# 4_Power_Management.net
KiCad netlist of a schematic drawn in Altium Designer
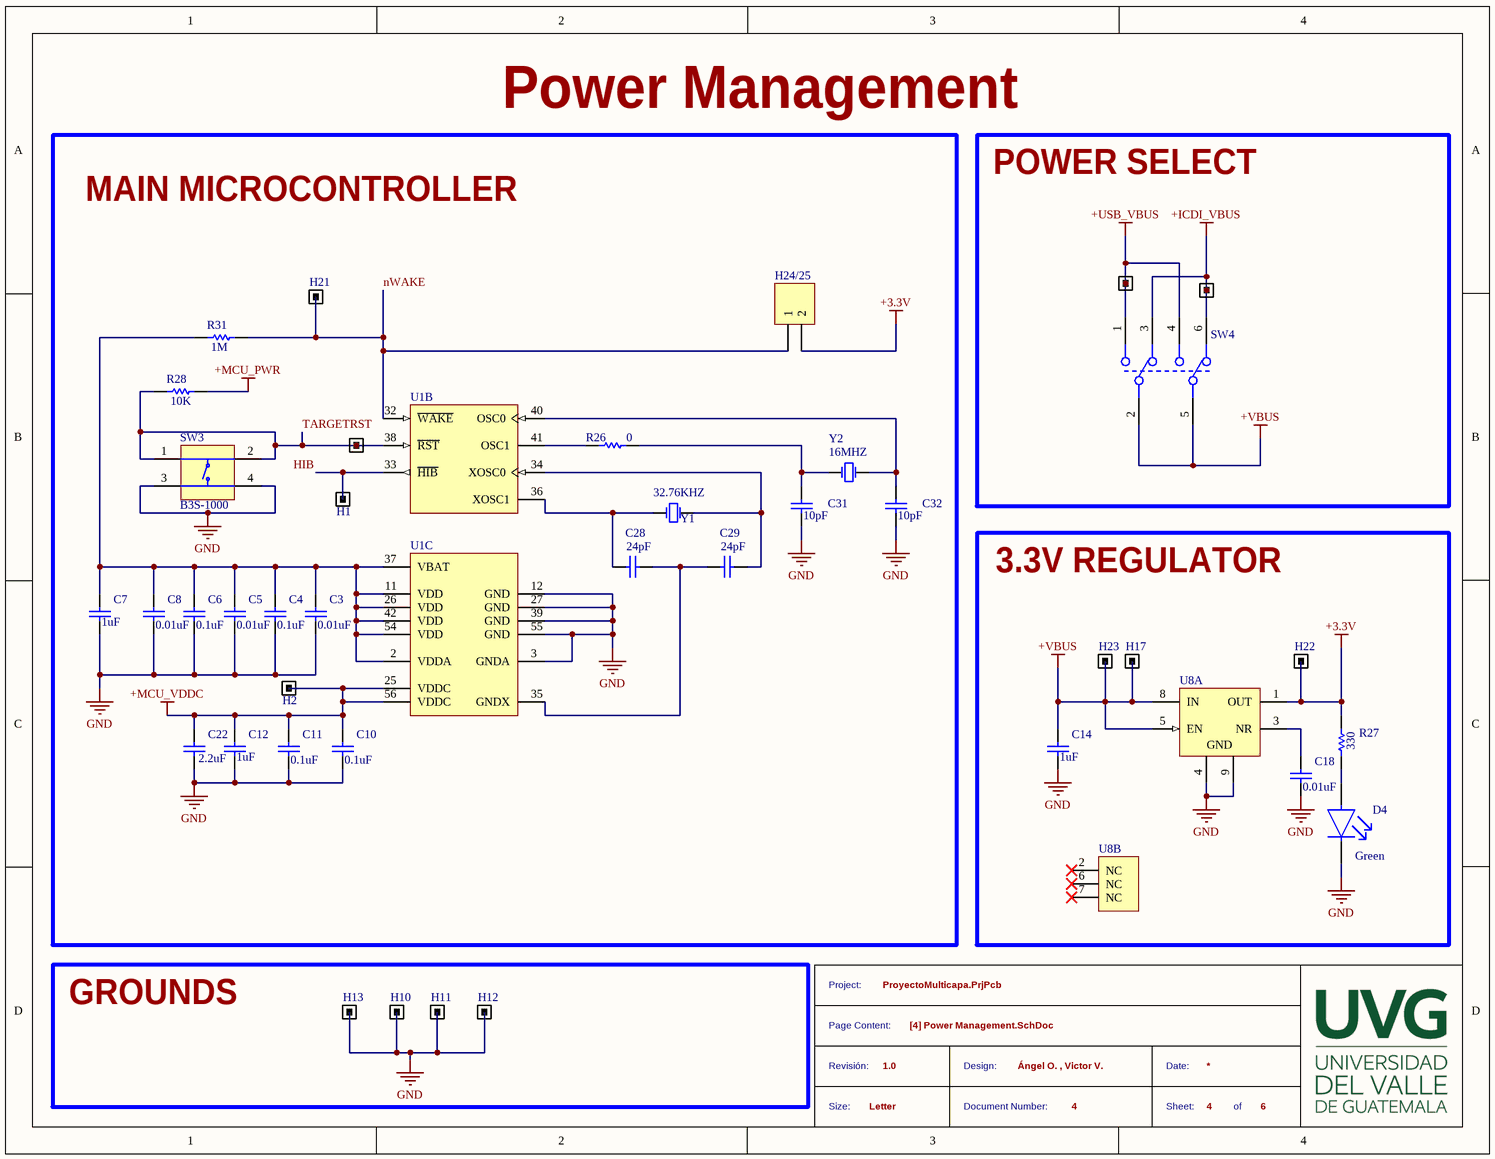
[diagram p0: [4] Power Management.SchDoc]

(export (version "E")
  (design (tool "Eeschema 10.0.6"))
  (components
    (comp (ref "C3")
      (value "EMK105B7103KV-F")
      (footprint "CAPC1005")
      (description "TAIYO YUDEN   EMK105B7103KV-F   CERAMIC CAPACITOR, 0.01UF, 16V, X7R, 10%, 0402, FULL REEL")
      (fields (field (name "MANUFACTURER") "Taiyo Yuden") (field (name "TOLERANCE") "10%"))
      (libsource (lib "LiberiaTivaC") (part "EMK105B7103KV-F"))
    )
    (comp (ref "C4")
      (value "EMK105B7104KV-F")
      (footprint "CAPC1005")
      (fields (field (name "MANUFACTURER") "Taiyo Yuden") (field (name "TOLERANCE") "10%"))
      (libsource (lib "LiberiaTivaC") (part "EMK105B7104KV-F"))
    )
    (comp (ref "C5")
      (value "EMK105B7103KV-F")
      (footprint "CAPC1005")
      (description "TAIYO YUDEN   EMK105B7103KV-F   CERAMIC CAPACITOR, 0.01UF, 16V, X7R, 10%, 0402, FULL REEL")
      (fields (field (name "MANUFACTURER") "Taiyo Yuden") (field (name "TOLERANCE") "10%"))
      (libsource (lib "LiberiaTivaC") (part "EMK105B7103KV-F"))
    )
    (comp (ref "C6")
      (value "EMK105B7104KV-F")
      (footprint "CAPC1005")
      (fields (field (name "MANUFACTURER") "Taiyo Yuden") (field (name "TOLERANCE") "10%"))
      (libsource (lib "LiberiaTivaC") (part "EMK105B7104KV-F"))
    )
    (comp (ref "C7")
      (value "capacitor Johanson Dielectrics Inc")
      (footprint "C0402 imperial")
      (description "Cap Ceramic 1uF 10V X5R 10% SMD 0402 85C T/R")
      (fields
        (field (name "MANUFACTURER") "Johanson")
        (field (name "MANUFACTURER PART NUMBER") "100R07X105KV4T")
      )
      (libsource (lib "Components") (part "100R07X105KV4T"))
    )
    (comp (ref "C8")
      (value "EMK105B7103KV-F")
      (footprint "CAPC1005")
      (description "TAIYO YUDEN   EMK105B7103KV-F   CERAMIC CAPACITOR, 0.01UF, 16V, X7R, 10%, 0402, FULL REEL")
      (fields (field (name "MANUFACTURER") "Taiyo Yuden") (field (name "TOLERANCE") "10%"))
      (libsource (lib "LiberiaTivaC") (part "EMK105B7103KV-F"))
    )
    (comp (ref "C10")
      (value "EMK105B7104KV-F")
      (footprint "CAPC1005")
      (fields (field (name "MANUFACTURER") "Taiyo Yuden") (field (name "TOLERANCE") "10%"))
      (libsource (lib "LiberiaTivaC") (part "EMK105B7104KV-F"))
    )
    (comp (ref "C11")
      (value "EMK105B7104KV-F")
      (footprint "CAPC1005")
      (fields (field (name "MANUFACTURER") "Taiyo Yuden") (field (name "TOLERANCE") "10%"))
      (libsource (lib "LiberiaTivaC") (part "EMK105B7104KV-F"))
    )
    (comp (ref "C12")
      (value "capacitor Johanson Dielectrics Inc")
      (footprint "C0402 imperial")
      (description "Cap Ceramic 1uF 10V X5R 10% SMD 0402 85C T/R")
      (fields
        (field (name "MANUFACTURER") "Johanson")
        (field (name "MANUFACTURER PART NUMBER") "100R07X105KV4T")
      )
      (libsource (lib "Components") (part "100R07X105KV4T"))
    )
    (comp (ref "C14")
      (value "capacitor Johanson Dielectrics Inc")
      (footprint "C0402 imperial")
      (description "Cap Ceramic 1uF 10V X5R 10% SMD 0402 85C T/R")
      (fields
        (field (name "MANUFACTURER") "Johanson")
        (field (name "MANUFACTURER PART NUMBER") "100R07X105KV4T")
      )
      (libsource (lib "Components") (part "100R07X105KV4T"))
    )
    (comp (ref "C18")
      (value "EMK105B7103KV-F")
      (footprint "CAPC1005")
      (description "TAIYO YUDEN   EMK105B7103KV-F   CERAMIC CAPACITOR, 0.01UF, 16V, X7R, 10%, 0402, FULL REEL")
      (fields (field (name "MANUFACTURER") "Taiyo Yuden") (field (name "TOLERANCE") "10%"))
      (libsource (lib "LiberiaTivaC") (part "EMK105B7103KV-F"))
    )
    (comp (ref "C22")
      (value "GRM188R61C225KE15D")
      (footprint "CAPC1608X90X35LL10T15")
      (description "Cap Ceramic 2.2uF 16V X5R 10% SMD 0603 85C Paper T/R")
      (fields (field (name "MANUFACTURER") "Murata") (field (name "TOLERANCE") "10%"))
      (libsource (lib "LiberiaTivaC") (part "GRM188R61C225KE15D"))
    )
    (comp (ref "C28")
      (value "Capacitor")
      (footprint "C0402 imperial")
      (description "CAP CER 24PF 50V C0G 0402")
      (fields (field (name "MANUFACTURER") "TDK") (field (name "MANUFACTURER PART NUMBER") "C1005C0G1H240J"))
      (libsource (lib "LiberiaTivaC") (part "C1005C0G1H240J"))
    )
    (comp (ref "C29")
      (value "Capacitor")
      (footprint "C0402 imperial")
      (description "CAP CER 24PF 50V C0G 0402")
      (fields (field (name "MANUFACTURER") "TDK") (field (name "MANUFACTURER PART NUMBER") "C1005C0G1H240J"))
      (libsource (lib "LiberiaTivaC") (part "C1005C0G1H240J"))
    )
    (comp (ref "C31")
      (value "GRM1555C1H100JZ01D")
      (footprint "CAPC1005X55X25LL05T10")
      (description "CAP, CERAMIC, 10PF, 50V, C0G/NP0, 0402")
      (fields (field (name "MANUFACTURER") "Murata") (field (name "TOLERANCE") "5%"))
      (libsource (lib "LiberiaTivaC") (part "GRM1555C1H100JZ01D"))
    )
    (comp (ref "C32")
      (value "GRM1555C1H100JZ01D")
      (footprint "CAPC1005X55X25LL05T10")
      (description "CAP, CERAMIC, 10PF, 50V, C0G/NP0, 0402")
      (fields (field (name "MANUFACTURER") "Murata") (field (name "TOLERANCE") "5%"))
      (libsource (lib "LiberiaTivaC") (part "GRM1555C1H100JZ01D"))
    )
    (comp (ref "D4")
      (value "Green")
      (footprint "FP-LTST-C171GKT-MFG")
      (description "LED GREEN CLEAR CHIP SMD")
      (fields
        (field (name "MANUFACTURER") "Vishay Lite-On")
        (field (name "MANUFACTURER PART NUMBER") "LTST-C171GKT")
      )
      (libsource (lib "LiberiaTivaC") (part "LTST-C171GKT"))
    )
    (comp (ref "H1")
      (value "header")
      (footprint "HEADER 1")
      (description "Pads header que aparecen en la tiva")
      (libsource (lib "LiberiaTivaC") (part "header"))
    )
    (comp (ref "H2")
      (value "header")
      (footprint "HEADER 1")
      (description "Pads header que aparecen en la tiva")
      (libsource (lib "LiberiaTivaC") (part "header"))
    )
    (comp (ref "H10")
      (value "header")
      (footprint "HEADER 1")
      (description "Pads header que aparecen en la tiva")
      (libsource (lib "LiberiaTivaC") (part "header"))
    )
    (comp (ref "H11")
      (value "header")
      (footprint "HEADER 1")
      (description "Pads header que aparecen en la tiva")
      (libsource (lib "LiberiaTivaC") (part "header"))
    )
    (comp (ref "H12")
      (value "header")
      (footprint "HEADER 1")
      (description "Pads header que aparecen en la tiva")
      (libsource (lib "LiberiaTivaC") (part "header"))
    )
    (comp (ref "H13")
      (value "header")
      (footprint "HEADER 1")
      (description "Pads header que aparecen en la tiva")
      (libsource (lib "LiberiaTivaC") (part "header"))
    )
    (comp (ref "H17")
      (value "header")
      (footprint "HEADER 1")
      (description "Pads header que aparecen en la tiva")
      (libsource (lib "LiberiaTivaC") (part "header"))
    )
    (comp (ref "H18")
      (value "header")
      (footprint "HEADER 1")
      (description "Pads header que aparecen en la tiva")
      (libsource (lib "LiberiaTivaC") (part "header"))
    )
    (comp (ref "H19")
      (value "header")
      (footprint "HEADER 1")
      (description "Pads header que aparecen en la tiva")
      (libsource (lib "LiberiaTivaC") (part "header"))
    )
    (comp (ref "H20")
      (value "header")
      (footprint "HEADER 1")
      (description "Pads header que aparecen en la tiva")
      (libsource (lib "LiberiaTivaC") (part "header"))
    )
    (comp (ref "H21")
      (value "header")
      (footprint "HEADER 1")
      (description "Pads header que aparecen en la tiva")
      (libsource (lib "LiberiaTivaC") (part "header"))
    )
    (comp (ref "H22")
      (value "header")
      (footprint "HEADER 1")
      (description "Pads header que aparecen en la tiva")
      (libsource (lib "LiberiaTivaC") (part "header"))
    )
    (comp (ref "H23")
      (value "header")
      (footprint "HEADER 1")
      (description "Pads header que aparecen en la tiva")
      (libsource (lib "LiberiaTivaC") (part "header"))
    )
    (comp (ref "H24/25")
      (value "Header 2")
      (footprint "HDR1X2")
      (description "Header, 2-Pin")
      (fields (field (name "PUBLISHER") "Altium Limited"))
      (libsource (lib "LiberiaTivaC") (part "Header 2"))
    )
    (comp (ref "R26")
      (value "ERJ-3GEY0R00V")
      (footprint "FP-ERJ-3GEY0R00V-IPC_A")
      (description "Res Thick Film 0603 0 Ohm Jumper Molded SMD Punched Carrier T/R")
      (fields (field (name "MANUFACTURER") "Panasonic") (field (name "TOLERANCE") "0%"))
      (libsource (lib "LiberiaTivaC") (part "ERJ-3GEY0R00V"))
    )
    (comp (ref "R27")
      (value "RC0402FR-07330RL")
      (footprint "RESC1005X40X25LL05T10")
      (description "Res Thick Film 0402 330 Ohm 1% 0.063W(1/16W) ±100ppm/C Pad SMD T/R")
      (fields (field (name "MANUFACTURER") "Yageo / Phycomp") (field (name "TOLERANCE") "1%"))
      (libsource (lib "LiberiaTivaC") (part "RC0402FR-07330RL"))
    )
    (comp (ref "R28")
      (value "RC0402FR-0710KL")
      (footprint "RESC1005X40X25LL05T10")
      (description "Surface Mount Thick Film Resistor, Rc Series, 10 Kohm, 62.5 Mw, - 1%, 50 V, 0402 [1005 Metric]")
      (fields (field (name "MANUFACTURER") "Yageo") (field (name "TOLERANCE") "1%"))
      (libsource (lib "LiberiaTivaC") (part "RC0402FR-0710KL"))
    )
    (comp (ref "R31")
      (value "MCR01MRTF1004")
      (footprint "RESC1005X40X25LL05T10")
      (description "RES SMD 1M OHM 1% 1/16W 0402")
      (fields (field (name "MANUFACTURER") "Rohm") (field (name "TOLERANCE") "1%"))
      (libsource (lib "LiberiaTivaC") (part "MCR01MRTF1004"))
    )
    (comp (ref "SW3")
      (value "B3S-1000")
      (footprint "OMRON-B3S-1000-4_V")
      (description "Sealed Tactile Switch, SPST-NO, 3 to 24 V, -25 to 70 degC, 4-Pin SMD, RoHS, Bulk")
      (fields (field (name "MANUFACTURER") "Omron"))
      (libsource (lib "LiberiaTivaC") (part "B3S-1000"))
    )
    (comp (ref "SW4")
      (value "JS202011SCQN")
      (footprint "FP-JS202011SCQN-MFG")
      (description "SWITCH SLIDE DPDT 300MA 6V")
      (libsource (lib "LiberiaTivaC") (part "JS202011SCQN"))
    )
    (comp (ref "U1")
      (value "TM4C123GH6PMIR")
      (footprint "PM0064A_L")
      (fields (field (name "MANUFACTURER") "Texas Instruments"))
      (libsource (lib "LiberiaTivaC") (part "TM4C123GH6PMI"))
    )
    (comp (ref "U8")
      (value "TPS73633DRBT")
      (footprint "DRB0008A_V")
      (fields (field (name "MANUFACTURER") "Texas Instruments"))
      (libsource (lib "LiberiaTivaC") (part "TPS73633DRBT"))
    )
    (comp (ref "Y1")
      (value "AB26TRB-32.768KHZ-T")
      (footprint "AB26TRB")
      (description "CRYSTAL 32.7680KHZ 12.5PF SMD")
      (fields
        (field (name "MOUSER PART NUMBER") "815-AB26TRB-32.76KHZ")
        (field (name "MANUFACTURER") "Abracon")
      )
      (libsource (lib "LiberiaTivaC") (part "AB26TRB-32.768KHZ-T"))
    )
    (comp (ref "Y2")
      (value "NX5032GA-16.000000MHZ")
      (footprint "NX5032GA16000000MHZLNCD1")
      (description "CRYSTAL 16.0000MHZ 8PF SMD")
      (fields
        (field (name "MANUFACTURER_PART_NUMBER") "NX5032GA-16.000000MHZ-LN-CD-1")
        (field (name "MANUFACTURER") "NDK")
      )
      (libsource (lib "LiberiaTivaC") (part "NX5032GA-16.000000MHZ"))
    )
  )
  (nets
    (net (code "1") (name "+3.3V") (class "Default")
      (node (ref "H22") (pin "1") (pinfunction "1_1") (pintype "passive"))
      (node (ref "H24/25") (pin "2") (pinfunction "2_2") (pintype "passive"))
      (node (ref "R27") (pin "2") (pinfunction "2_2") (pintype "passive"))
      (node (ref "U8") (pin "1") (pinfunction "OUT_1") (pintype "power_in"))
    )
    (net (code "2") (name "+ICDI_VBUS") (class "Default")
      (node (ref "H19") (pin "1") (pinfunction "1_1") (pintype "passive"))
      (node (ref "SW4") (pin "3") (pinfunction "3_3") (pintype "passive"))
      (node (ref "SW4") (pin "6") (pinfunction "6_6") (pintype "passive"))
    )
    (net (code "3") (name "+MCU_PWR") (class "Default")
      (node (ref "R28") (pin "2") (pinfunction "2_2") (pintype "passive"))
    )
    (net (code "4") (name "+MCU_VDDC") (class "Default")
      (node (ref "C10") (pin "1") (pinfunction "1_1") (pintype "passive"))
      (node (ref "C11") (pin "1") (pinfunction "1_1") (pintype "passive"))
      (node (ref "C12") (pin "1") (pinfunction "1_1") (pintype "passive"))
      (node (ref "C22") (pin "1") (pinfunction "1_1") (pintype "passive"))
      (node (ref "H2") (pin "1") (pinfunction "1_1") (pintype "passive"))
      (node (ref "U1") (pin "25") (pinfunction "VDDC_25") (pintype "power_in"))
      (node (ref "U1") (pin "56") (pinfunction "VDDC_56") (pintype "power_in"))
    )
    (net (code "5") (name "+USB_VBUS") (class "Default")
      (node (ref "H18") (pin "1") (pinfunction "1_1") (pintype "passive"))
      (node (ref "SW4") (pin "1") (pinfunction "1_1") (pintype "passive"))
      (node (ref "SW4") (pin "4") (pinfunction "4_4") (pintype "passive"))
    )
    (net (code "6") (name "+VBUS") (class "Default")
      (node (ref "C14") (pin "1") (pinfunction "1_1") (pintype "passive"))
      (node (ref "H17") (pin "1") (pinfunction "1_1") (pintype "passive"))
      (node (ref "H23") (pin "1") (pinfunction "1_1") (pintype "passive"))
      (node (ref "SW4") (pin "2") (pinfunction "2_2") (pintype "passive"))
      (node (ref "SW4") (pin "5") (pinfunction "5_5") (pintype "passive"))
      (node (ref "U8") (pin "5") (pinfunction "EN_5") (pintype "input"))
      (node (ref "U8") (pin "8") (pinfunction "IN_8") (pintype "power_in"))
    )
    (net (code "7") (name "/HIB") (class "Default")
      (node (ref "H1") (pin "1") (pinfunction "1_1") (pintype "passive"))
      (node (ref "U1") (pin "33") (pinfunction "~{HIB}_33") (pintype "output"))
    )
    (net (code "8") (name "/TARGETRST") (class "Default")
      (node (ref "H20") (pin "1") (pinfunction "1_1") (pintype "passive"))
      (node (ref "R28") (pin "1") (pinfunction "1_1") (pintype "passive"))
      (node (ref "SW3") (pin "1") (pinfunction "1_1") (pintype "passive"))
      (node (ref "SW3") (pin "2") (pinfunction "2_2") (pintype "passive"))
      (node (ref "U1") (pin "38") (pinfunction "~{RST}_38") (pintype "input"))
    )
    (net (code "9") (name "/nWAKE") (class "Default")
      (node (ref "H21") (pin "1") (pinfunction "1_1") (pintype "passive"))
      (node (ref "H24/25") (pin "1") (pinfunction "1_1") (pintype "passive"))
      (node (ref "R31") (pin "2") (pinfunction "2_2") (pintype "passive"))
      (node (ref "U1") (pin "32") (pinfunction "~{WAKE}_32") (pintype "input"))
    )
    (net (code "10") (name "GND") (class "Default")
      (node (ref "C10") (pin "2") (pinfunction "2_2") (pintype "passive"))
      (node (ref "C11") (pin "2") (pinfunction "2_2") (pintype "passive"))
      (node (ref "C12") (pin "2") (pinfunction "2_2") (pintype "passive"))
      (node (ref "C14") (pin "2") (pinfunction "2_2") (pintype "passive"))
      (node (ref "C18") (pin "2") (pinfunction "2_2") (pintype "passive"))
      (node (ref "C22") (pin "2") (pinfunction "2_2") (pintype "passive"))
      (node (ref "C3") (pin "2") (pinfunction "2_2") (pintype "passive"))
      (node (ref "C31") (pin "2") (pinfunction "2_2") (pintype "passive"))
      (node (ref "C32") (pin "2") (pinfunction "2_2") (pintype "passive"))
      (node (ref "C4") (pin "2") (pinfunction "2_2") (pintype "passive"))
      (node (ref "C5") (pin "2") (pinfunction "2_2") (pintype "passive"))
      (node (ref "C6") (pin "2") (pinfunction "2_2") (pintype "passive"))
      (node (ref "C7") (pin "2") (pinfunction "2_2") (pintype "passive"))
      (node (ref "C8") (pin "2") (pinfunction "2_2") (pintype "passive"))
      (node (ref "D4") (pin "1") (pinfunction "C_1") (pintype "passive"))
      (node (ref "H10") (pin "1") (pinfunction "1_1") (pintype "passive"))
      (node (ref "H11") (pin "1") (pinfunction "1_1") (pintype "passive"))
      (node (ref "H12") (pin "1") (pinfunction "1_1") (pintype "passive"))
      (node (ref "H13") (pin "1") (pinfunction "1_1") (pintype "passive"))
      (node (ref "SW3") (pin "3") (pinfunction "3_3") (pintype "passive"))
      (node (ref "SW3") (pin "4") (pinfunction "4_4") (pintype "passive"))
      (node (ref "U1") (pin "12") (pinfunction "GND_12") (pintype "power_in"))
      (node (ref "U1") (pin "27") (pinfunction "GND_27") (pintype "power_in"))
      (node (ref "U1") (pin "3") (pinfunction "GNDA_3") (pintype "power_in"))
      (node (ref "U1") (pin "39") (pinfunction "GND_39") (pintype "power_in"))
      (node (ref "U1") (pin "55") (pinfunction "GND_55") (pintype "power_in"))
      (node (ref "U8") (pin "4") (pinfunction "GND_4") (pintype "power_in"))
      (node (ref "U8") (pin "9") (pinfunction "GND_9") (pintype "power_in"))
    )
    (net (code "11") (name "Net-(C31-Pad1)") (class "Default")
      (node (ref "C31") (pin "1") (pinfunction "1_1") (pintype "passive"))
      (node (ref "R26") (pin "2") (pinfunction "2_2") (pintype "passive"))
      (node (ref "Y2") (pin "1") (pinfunction "1_1") (pintype "passive"))
    )
    (net (code "12") (name "Net-(D4-A)") (class "Default")
      (node (ref "D4") (pin "2") (pinfunction "A_2") (pintype "passive"))
      (node (ref "R27") (pin "1") (pinfunction "1_1") (pintype "passive"))
    )
    (net (code "13") (name "Net-(U1B-OSC0)") (class "Default")
      (node (ref "C32") (pin "1") (pinfunction "1_1") (pintype "passive"))
      (node (ref "U1") (pin "40") (pinfunction "OSC0_40") (pintype "input"))
      (node (ref "Y2") (pin "2") (pinfunction "2_2") (pintype "passive"))
    )
    (net (code "14") (name "Net-(U1B-OSC1)") (class "Default")
      (node (ref "R26") (pin "1") (pinfunction "1_1") (pintype "passive"))
      (node (ref "U1") (pin "41") (pinfunction "OSC1_41") (pintype "passive"))
    )
    (net (code "15") (name "Net-(U1B-XOSC0)") (class "Default")
      (node (ref "C29") (pin "2") (pinfunction "2_2") (pintype "passive"))
      (node (ref "U1") (pin "34") (pinfunction "XOSC0_34") (pintype "input"))
      (node (ref "Y1") (pin "2") (pinfunction "2_2") (pintype "passive"))
    )
    (net (code "16") (name "Net-(U1B-XOSC1)") (class "Default")
      (node (ref "C28") (pin "1") (pinfunction "1_1") (pintype "passive"))
      (node (ref "U1") (pin "36") (pinfunction "XOSC1_36") (pintype "passive"))
      (node (ref "Y1") (pin "1") (pinfunction "1_1") (pintype "passive"))
    )
    (net (code "17") (name "Net-(U1C-GNDX)") (class "Default")
      (node (ref "C28") (pin "2") (pinfunction "2_2") (pintype "passive"))
      (node (ref "C29") (pin "1") (pinfunction "1_1") (pintype "passive"))
      (node (ref "U1") (pin "35") (pinfunction "GNDX_35") (pintype "power_in"))
    )
    (net (code "18") (name "Net-(U1C-VBAT)") (class "Default")
      (node (ref "C3") (pin "1") (pinfunction "1_1") (pintype "passive"))
      (node (ref "C4") (pin "1") (pinfunction "1_1") (pintype "passive"))
      (node (ref "C5") (pin "1") (pinfunction "1_1") (pintype "passive"))
      (node (ref "C6") (pin "1") (pinfunction "1_1") (pintype "passive"))
      (node (ref "C7") (pin "1") (pinfunction "1_1") (pintype "passive"))
      (node (ref "C8") (pin "1") (pinfunction "1_1") (pintype "passive"))
      (node (ref "R31") (pin "1") (pinfunction "1_1") (pintype "passive"))
      (node (ref "U1") (pin "11") (pinfunction "VDD_11") (pintype "power_in"))
      (node (ref "U1") (pin "2") (pinfunction "VDDA_2") (pintype "power_in"))
      (node (ref "U1") (pin "26") (pinfunction "VDD_26") (pintype "power_in"))
      (node (ref "U1") (pin "37") (pinfunction "VBAT_37") (pintype "power_in"))
      (node (ref "U1") (pin "42") (pinfunction "VDD_42") (pintype "power_in"))
      (node (ref "U1") (pin "54") (pinfunction "VDD_54") (pintype "power_in"))
    )
    (net (code "19") (name "Net-(U8A-NR)") (class "Default")
      (node (ref "C18") (pin "1") (pinfunction "1_1") (pintype "passive"))
      (node (ref "U8") (pin "3") (pinfunction "NR_3") (pintype "passive"))
    )
    (net (code "20") (name "unconnected-(U8B-NC-Pad2)") (class "Default")
      (node (ref "U8") (pin "2") (pinfunction "NC_2") (pintype "passive+no_connect"))
    )
    (net (code "21") (name "unconnected-(U8B-NC-Pad6)") (class "Default")
      (node (ref "U8") (pin "6") (pinfunction "NC_6") (pintype "passive+no_connect"))
    )
    (net (code "22") (name "unconnected-(U8B-NC-Pad7)") (class "Default")
      (node (ref "U8") (pin "7") (pinfunction "NC_7") (pintype "passive+no_connect"))
    )
  )
)
